# some_mini_things.net
KiCad netlist of a schematic drawn in Altium Designer
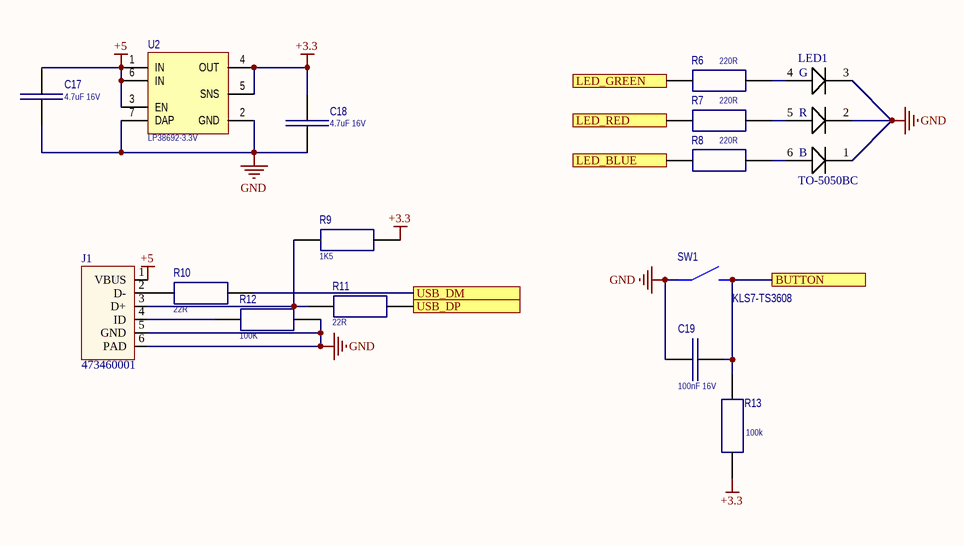
[diagram p0: some_mini_things.SchDoc]

(export (version "E")
  (design (tool "Eeschema 10.0.6"))
  (components
    (comp (ref "C17")
      (value "4.7uF 16V")
      (footprint "C_0805")
      (description "Capacitor")
      (libsource (lib "AX_Altium_v2.3") (part "C0805"))
    )
    (comp (ref "C18")
      (value "4.7uF 16V")
      (footprint "C_0805")
      (description "Capacitor")
      (libsource (lib "AX_Altium_v2.3") (part "C0805"))
    )
    (comp (ref "C19")
      (value "100nF 16V")
      (footprint "C_0805")
      (description "Capacitor")
      (libsource (lib "AX_Altium_v2.3") (part "C0805"))
    )
    (comp (ref "J1")
      (value "473460001")
      (footprint "micro-USB")
      (description "molex 473460001")
      (libsource (lib "usb") (part "MICRO-USB"))
    )
    (comp (ref "LED1")
      (value "TO-5050BC")
      (footprint "TO-5050BC")
      (description "RGB led")
      (libsource (lib "LED") (part "TO-5050BC"))
    )
    (comp (ref "R6")
      (value "220R")
      (footprint "R_0805")
      (description "Resistor")
      (libsource (lib "AX_Altium_v2.3") (part "R0805"))
    )
    (comp (ref "R7")
      (value "220R")
      (footprint "R_0805")
      (description "Resistor")
      (libsource (lib "AX_Altium_v2.3") (part "R0805"))
    )
    (comp (ref "R8")
      (value "220R")
      (footprint "R_0805")
      (description "Resistor")
      (libsource (lib "AX_Altium_v2.3") (part "R0805"))
    )
    (comp (ref "R9")
      (value "1K5")
      (footprint "R_0805")
      (description "Resistor")
      (libsource (lib "AX_Altium_v2.3") (part "R0805"))
    )
    (comp (ref "R10")
      (value "22R")
      (footprint "R_0805")
      (description "Resistor")
      (libsource (lib "AX_Altium_v2.3") (part "R0805"))
    )
    (comp (ref "R11")
      (value "22R")
      (footprint "R_0805")
      (description "Resistor")
      (libsource (lib "AX_Altium_v2.3") (part "R0805"))
    )
    (comp (ref "R12")
      (value "100K")
      (footprint "R_0805")
      (description "Resistor")
      (libsource (lib "AX_Altium_v2.3") (part "R0805"))
    )
    (comp (ref "R13")
      (value "100k")
      (footprint "R_0805")
      (description "Resistor")
      (libsource (lib "AX_Altium_v2.3") (part "R0805"))
    )
    (comp (ref "SW1")
      (value "KLS7-TS3608")
      (footprint "KLS7-TS3611")
      (libsource (lib "ConnectorButtonSocetDisplay") (part "button"))
    )
    (comp (ref "U2")
      (value "LP38692-3.3V")
      (footprint "AX_Altium_v2.3:WSON-6")
      (description "LP38690, LP38692 1-A LDO CMOS Linear Regulators  Stable with Ceramic Output Capacitors")
      (libsource (lib "AX_Altium_v2.3") (part "LP38692"))
    )
  )
  (nets
    (net (code "1") (name "+3.3") (class "Default")
      (node (ref "C18") (pin "2") (pinfunction "2_2") (pintype "passive"))
      (node (ref "R13") (pin "1") (pinfunction "1_1") (pintype "passive"))
      (node (ref "R9") (pin "2") (pinfunction "2_2") (pintype "passive"))
      (node (ref "U2") (pin "4") (pinfunction "OUT_4") (pintype "passive"))
      (node (ref "U2") (pin "5") (pinfunction "SNS_5") (pintype "passive"))
    )
    (net (code "2") (name "+5") (class "Default")
      (node (ref "C17") (pin "2") (pinfunction "2_2") (pintype "passive"))
      (node (ref "J1") (pin "1") (pinfunction "VBUS_1") (pintype "passive"))
      (node (ref "U2") (pin "1") (pinfunction "IN_1") (pintype "passive"))
      (node (ref "U2") (pin "3") (pinfunction "EN_3") (pintype "passive"))
      (node (ref "U2") (pin "6") (pinfunction "IN_6") (pintype "passive"))
    )
    (net (code "3") (name "/BUTTON") (class "Default")
      (node (ref "C19") (pin "1") (pinfunction "1_1") (pintype "passive"))
      (node (ref "R13") (pin "2") (pinfunction "2_2") (pintype "passive"))
      (node (ref "SW1") (pin "2") (pinfunction "2_2") (pintype "passive"))
    )
    (net (code "4") (name "/LED_BLUE") (class "Default")
      (node (ref "R8") (pin "1") (pinfunction "1_1") (pintype "passive"))
    )
    (net (code "5") (name "/LED_GREEN") (class "Default")
      (node (ref "R6") (pin "1") (pinfunction "1_1") (pintype "passive"))
    )
    (net (code "6") (name "/LED_RED") (class "Default")
      (node (ref "R7") (pin "1") (pinfunction "1_1") (pintype "passive"))
    )
    (net (code "7") (name "/USB_DM") (class "Default")
      (node (ref "R10") (pin "2") (pinfunction "2_2") (pintype "passive"))
    )
    (net (code "8") (name "/USB_DP") (class "Default")
      (node (ref "R11") (pin "2") (pinfunction "2_2") (pintype "passive"))
    )
    (net (code "9") (name "GND") (class "Default")
      (node (ref "C17") (pin "1") (pinfunction "1_1") (pintype "passive"))
      (node (ref "C18") (pin "1") (pinfunction "1_1") (pintype "passive"))
      (node (ref "C19") (pin "2") (pinfunction "2_2") (pintype "passive"))
      (node (ref "J1") (pin "5") (pinfunction "GND_5") (pintype "passive"))
      (node (ref "J1") (pin "6") (pinfunction "PAD_6") (pintype "passive"))
      (node (ref "LED1") (pin "1") (pintype "passive"))
      (node (ref "LED1") (pin "2") (pintype "passive"))
      (node (ref "LED1") (pin "3") (pintype "passive"))
      (node (ref "R12") (pin "2") (pinfunction "2_2") (pintype "passive"))
      (node (ref "SW1") (pin "1") (pinfunction "1_1") (pintype "passive"))
      (node (ref "U2") (pin "2") (pinfunction "GND_2") (pintype "passive"))
      (node (ref "U2") (pin "7") (pinfunction "DAP_7") (pintype "passive"))
    )
    (net (code "10") (name "Net-(J1-D+)") (class "Default")
      (node (ref "J1") (pin "3") (pinfunction "D+_3") (pintype "passive"))
      (node (ref "R11") (pin "1") (pinfunction "1_1") (pintype "passive"))
      (node (ref "R9") (pin "1") (pinfunction "1_1") (pintype "passive"))
    )
    (net (code "11") (name "Net-(J1-D-)") (class "Default")
      (node (ref "J1") (pin "2") (pinfunction "D-_2") (pintype "passive"))
      (node (ref "R10") (pin "1") (pinfunction "1_1") (pintype "passive"))
    )
    (net (code "12") (name "Net-(J1-ID)") (class "Default")
      (node (ref "J1") (pin "4") (pinfunction "ID_4") (pintype "passive"))
      (node (ref "R12") (pin "1") (pinfunction "1_1") (pintype "passive"))
    )
    (net (code "13") (name "Net-(LED1-Pad4)") (class "Default")
      (node (ref "LED1") (pin "4") (pintype "passive"))
      (node (ref "R6") (pin "2") (pinfunction "2_2") (pintype "passive"))
    )
    (net (code "14") (name "Net-(LED1-Pad5)") (class "Default")
      (node (ref "LED1") (pin "5") (pintype "passive"))
      (node (ref "R7") (pin "2") (pinfunction "2_2") (pintype "passive"))
    )
    (net (code "15") (name "Net-(LED1-Pad6)") (class "Default")
      (node (ref "LED1") (pin "6") (pintype "passive"))
      (node (ref "R8") (pin "2") (pinfunction "2_2") (pintype "passive"))
    )
  )
)
